# PowerGroup.net
KiCad netlist of a schematic drawn in Altium Designer
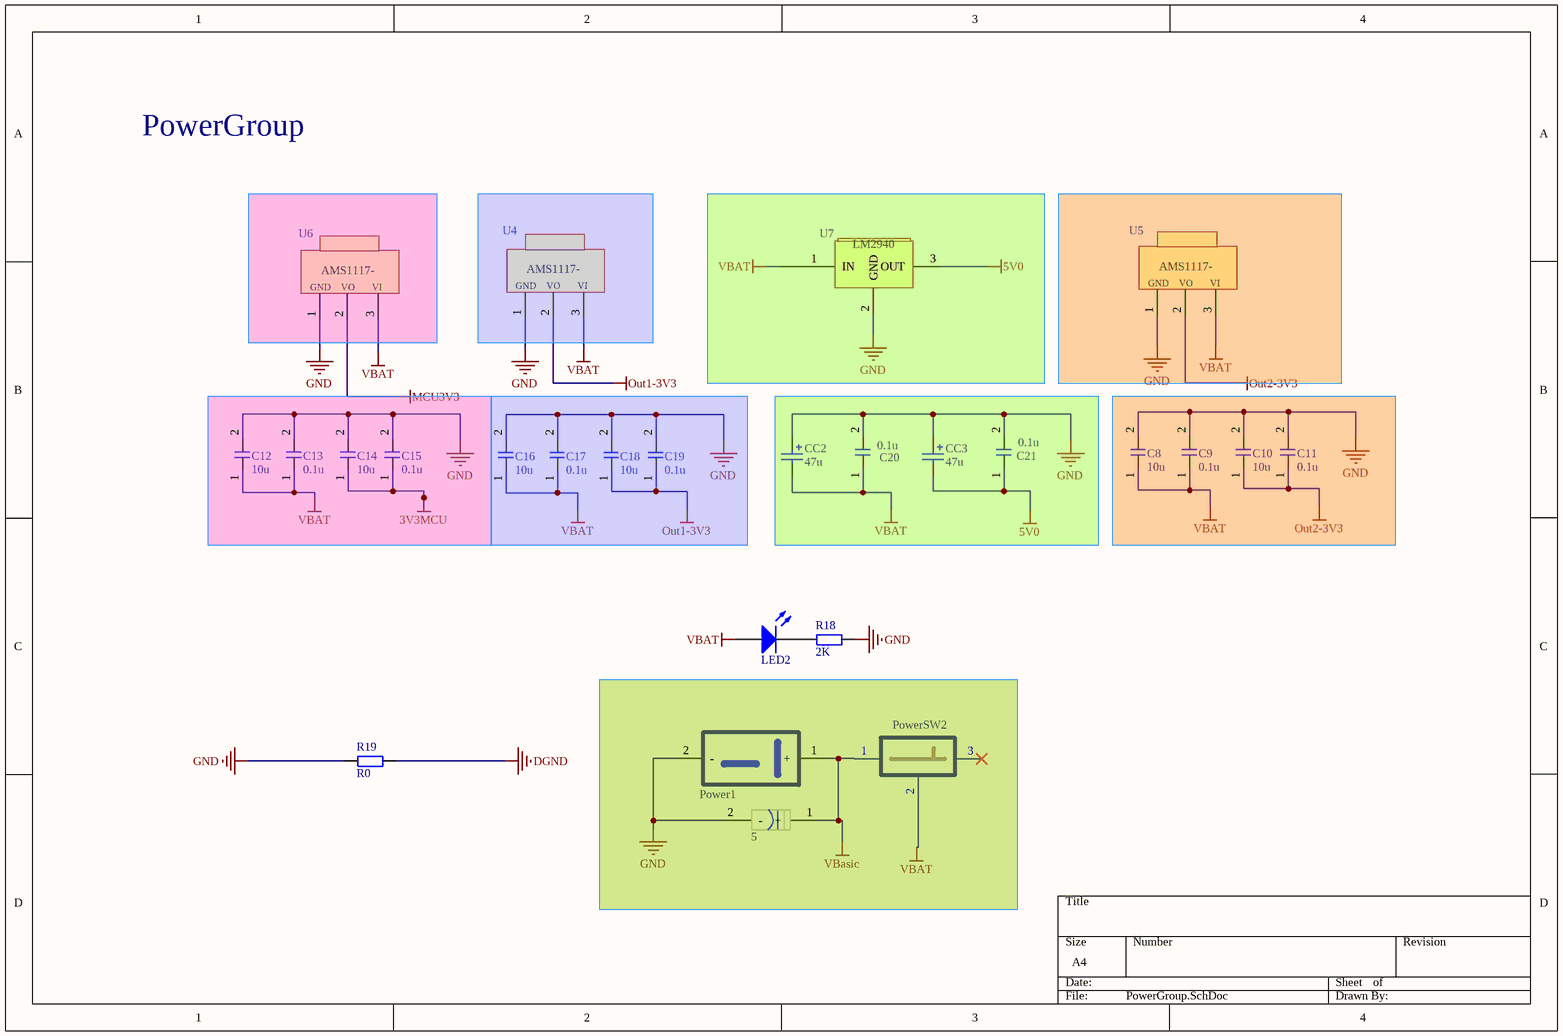
[diagram p0: PowerGroup.SchDoc]

(export (version "E")
  (design (tool "Eeschema 10.0.6"))
  (components
    (comp (ref "5") (value "钽电容") (footprint "钽D") (libsource (lib "常用原件库") (part "钽电容")))
    (comp (ref "C8") (value "10u") (footprint "0805电容") (libsource (lib "常用原件库") (part "0805电容")))
    (comp (ref "C9") (value "0.1u") (footprint "0805电容") (libsource (lib "常用原件库") (part "0805电容")))
    (comp (ref "C10") (value "10u") (footprint "0805电容") (libsource (lib "常用原件库") (part "0805电容")))
    (comp (ref "C11") (value "0.1u") (footprint "0805电容") (libsource (lib "常用原件库") (part "0805电容")))
    (comp (ref "C12") (value "10u") (footprint "0805电容") (libsource (lib "常用原件库") (part "0805电容")))
    (comp (ref "C13") (value "0.1u") (footprint "0805电容") (libsource (lib "常用原件库") (part "0805电容")))
    (comp (ref "C14") (value "10u") (footprint "0805电容") (libsource (lib "常用原件库") (part "0805电容")))
    (comp (ref "C15") (value "0.1u") (footprint "0805电容") (libsource (lib "常用原件库") (part "0805电容")))
    (comp (ref "C16") (value "10u") (footprint "0805电容") (libsource (lib "常用原件库") (part "0805电容")))
    (comp (ref "C17") (value "0.1u") (footprint "0805电容") (libsource (lib "常用原件库") (part "0805电容")))
    (comp (ref "C18") (value "10u") (footprint "0805电容") (libsource (lib "常用原件库") (part "0805电容")))
    (comp (ref "C19") (value "0.1u") (footprint "0805电容") (libsource (lib "常用原件库") (part "0805电容")))
    (comp (ref "C20") (value "0.1u") (footprint "0805电容") (libsource (lib "常用原件库") (part "0805电容")))
    (comp (ref "C21") (value "0.1u") (footprint "0805电容") (libsource (lib "常用原件库") (part "0805电容")))
    (comp (ref "CC2")
      (value "Cap Tan C")
      (footprint "CAPMP6032X26N")
      (description "Polarized Capacitor (Radial)")
      (fields
        (field (name "CAPACITANCE") "47u")
        (field (name "VOLTAGE") "16V")
        (field (name "PUBLISHER") "Altium Limited")
      )
      (libsource (lib "ZZCDevice") (part "Cap Tan C"))
    )
    (comp (ref "CC3")
      (value "Cap Tan C")
      (footprint "CAPMP6032X26N")
      (description "Polarized Capacitor (Radial)")
      (fields
        (field (name "CAPACITANCE") "47u")
        (field (name "VOLTAGE") "16V")
        (field (name "PUBLISHER") "Altium Limited")
      )
      (libsource (lib "ZZCDevice") (part "Cap Tan C"))
    )
    (comp (ref "LED2") (value "0805LED") (footprint "0805LED") (libsource (lib "常用原件库") (part "0805LED")))
    (comp (ref "Power1") (value "XT60") (footprint "XT60") (libsource (lib "ZZCDevice") (part "XT60")))
    (comp (ref "PowerSW2")
      (value "Power")
      (footprint "PowerSW")
      (libsource (lib "ZZCDevice") (part "PowerSW"))
    )
    (comp (ref "R18") (value "2K") (footprint "0805电阻") (libsource (lib "常用原件库") (part "0805电阻")))
    (comp (ref "R19") (value "R0") (footprint "0805电阻") (libsource (lib "常用原件库") (part "0805电阻")))
    (comp (ref "U4") (value "AMS1117-") (footprint "AMS1117-") (libsource (lib "常用原件库") (part "AMS1117-")))
    (comp (ref "U5") (value "AMS1117-") (footprint "AMS1117-") (libsource (lib "常用原件库") (part "AMS1117-")))
    (comp (ref "U6") (value "AMS1117-") (footprint "AMS1117-") (libsource (lib "常用原件库") (part "AMS1117-")))
    (comp (ref "U7") (value "LM2940") (footprint "LM2940") (libsource (lib "常用原件库") (part "LM2940")))
  )
  (nets
    (net (code "1") (name "3V3MCU") (class "Default")
      (node (ref "C14") (pin "1") (pinfunction "1_1") (pintype "passive"))
      (node (ref "C15") (pin "1") (pinfunction "1_1") (pintype "passive"))
    )
    (net (code "2") (name "5V0") (class "Default")
      (node (ref "C21") (pin "1") (pinfunction "1_1") (pintype "passive"))
      (node (ref "CC3") (pin "1") (pinfunction "2_1") (pintype "passive"))
      (node (ref "U7") (pin "3") (pinfunction "OUT_3") (pintype "passive"))
    )
    (net (code "3") (name "DGND") (class "Default")
      (node (ref "R19") (pin "1") (pinfunction "1_1") (pintype "passive"))
    )
    (net (code "4") (name "GND") (class "Default")
      (node (ref "5") (pin "2") (pinfunction "-_2") (pintype "passive"))
      (node (ref "C10") (pin "2") (pinfunction "2_2") (pintype "passive"))
      (node (ref "C11") (pin "2") (pinfunction "2_2") (pintype "passive"))
      (node (ref "C12") (pin "2") (pinfunction "2_2") (pintype "passive"))
      (node (ref "C13") (pin "2") (pinfunction "2_2") (pintype "passive"))
      (node (ref "C14") (pin "2") (pinfunction "2_2") (pintype "passive"))
      (node (ref "C15") (pin "2") (pinfunction "2_2") (pintype "passive"))
      (node (ref "C16") (pin "2") (pinfunction "2_2") (pintype "passive"))
      (node (ref "C17") (pin "2") (pinfunction "2_2") (pintype "passive"))
      (node (ref "C18") (pin "2") (pinfunction "2_2") (pintype "passive"))
      (node (ref "C19") (pin "2") (pinfunction "2_2") (pintype "passive"))
      (node (ref "C20") (pin "2") (pinfunction "2_2") (pintype "passive"))
      (node (ref "C21") (pin "2") (pinfunction "2_2") (pintype "passive"))
      (node (ref "C8") (pin "2") (pinfunction "2_2") (pintype "passive"))
      (node (ref "C9") (pin "2") (pinfunction "2_2") (pintype "passive"))
      (node (ref "CC2") (pin "2") (pinfunction "1_2") (pintype "passive"))
      (node (ref "CC3") (pin "2") (pinfunction "1_2") (pintype "passive"))
      (node (ref "Power1") (pin "2") (pinfunction "-_2") (pintype "passive"))
      (node (ref "R18") (pin "1") (pinfunction "1_1") (pintype "passive"))
      (node (ref "R19") (pin "2") (pinfunction "2_2") (pintype "passive"))
      (node (ref "U4") (pin "1") (pinfunction "GND_1") (pintype "passive"))
      (node (ref "U5") (pin "1") (pinfunction "GND_1") (pintype "passive"))
      (node (ref "U6") (pin "1") (pinfunction "GND_1") (pintype "passive"))
      (node (ref "U7") (pin "2") (pinfunction "GND_2") (pintype "passive"))
    )
    (net (code "5") (name "MCU3V3") (class "Default")
      (node (ref "U6") (pin "2") (pinfunction "Vout_2") (pintype "passive"))
    )
    (net (code "6") (name "Net-(LED2-K)") (class "Default")
      (node (ref "LED2") (pin "2") (pinfunction "K_2") (pintype "passive"))
      (node (ref "R18") (pin "2") (pinfunction "2_2") (pintype "passive"))
    )
    (net (code "7") (name "Out1-3V3") (class "Default")
      (node (ref "C18") (pin "1") (pinfunction "1_1") (pintype "passive"))
      (node (ref "C19") (pin "1") (pinfunction "1_1") (pintype "passive"))
      (node (ref "U4") (pin "2") (pinfunction "Vout_2") (pintype "passive"))
    )
    (net (code "8") (name "Out2-3V3") (class "Default")
      (node (ref "C10") (pin "1") (pinfunction "1_1") (pintype "passive"))
      (node (ref "C11") (pin "1") (pinfunction "1_1") (pintype "passive"))
      (node (ref "U5") (pin "2") (pinfunction "Vout_2") (pintype "passive"))
    )
    (net (code "9") (name "VBAT") (class "Default")
      (node (ref "C12") (pin "1") (pinfunction "1_1") (pintype "passive"))
      (node (ref "C13") (pin "1") (pinfunction "1_1") (pintype "passive"))
      (node (ref "C16") (pin "1") (pinfunction "1_1") (pintype "passive"))
      (node (ref "C17") (pin "1") (pinfunction "1_1") (pintype "passive"))
      (node (ref "C20") (pin "1") (pinfunction "1_1") (pintype "passive"))
      (node (ref "C8") (pin "1") (pinfunction "1_1") (pintype "passive"))
      (node (ref "C9") (pin "1") (pinfunction "1_1") (pintype "passive"))
      (node (ref "CC2") (pin "1") (pinfunction "2_1") (pintype "passive"))
      (node (ref "LED2") (pin "1") (pinfunction "A_1") (pintype "passive"))
      (node (ref "PowerSW2") (pin "2") (pinfunction "2_2") (pintype "passive"))
      (node (ref "U4") (pin "3") (pinfunction "Vin_3") (pintype "passive"))
      (node (ref "U5") (pin "3") (pinfunction "Vin_3") (pintype "passive"))
      (node (ref "U6") (pin "3") (pinfunction "Vin_3") (pintype "passive"))
      (node (ref "U7") (pin "1") (pinfunction "IN_1") (pintype "passive"))
    )
    (net (code "10") (name "VBasic") (class "Default")
      (node (ref "5") (pin "1") (pinfunction "+_1") (pintype "passive"))
      (node (ref "Power1") (pin "1") (pinfunction "+_1") (pintype "passive"))
      (node (ref "PowerSW2") (pin "1") (pinfunction "1_1") (pintype "passive"))
    )
    (net (code "11") (name "unconnected-(PowerSW2-Pad3)") (class "Default")
      (node (ref "PowerSW2") (pin "3") (pinfunction "3_3") (pintype "passive+no_connect"))
    )
  )
)
